# rfid_module_v1.net
KiCad netlist of a schematic drawn in EAGLE
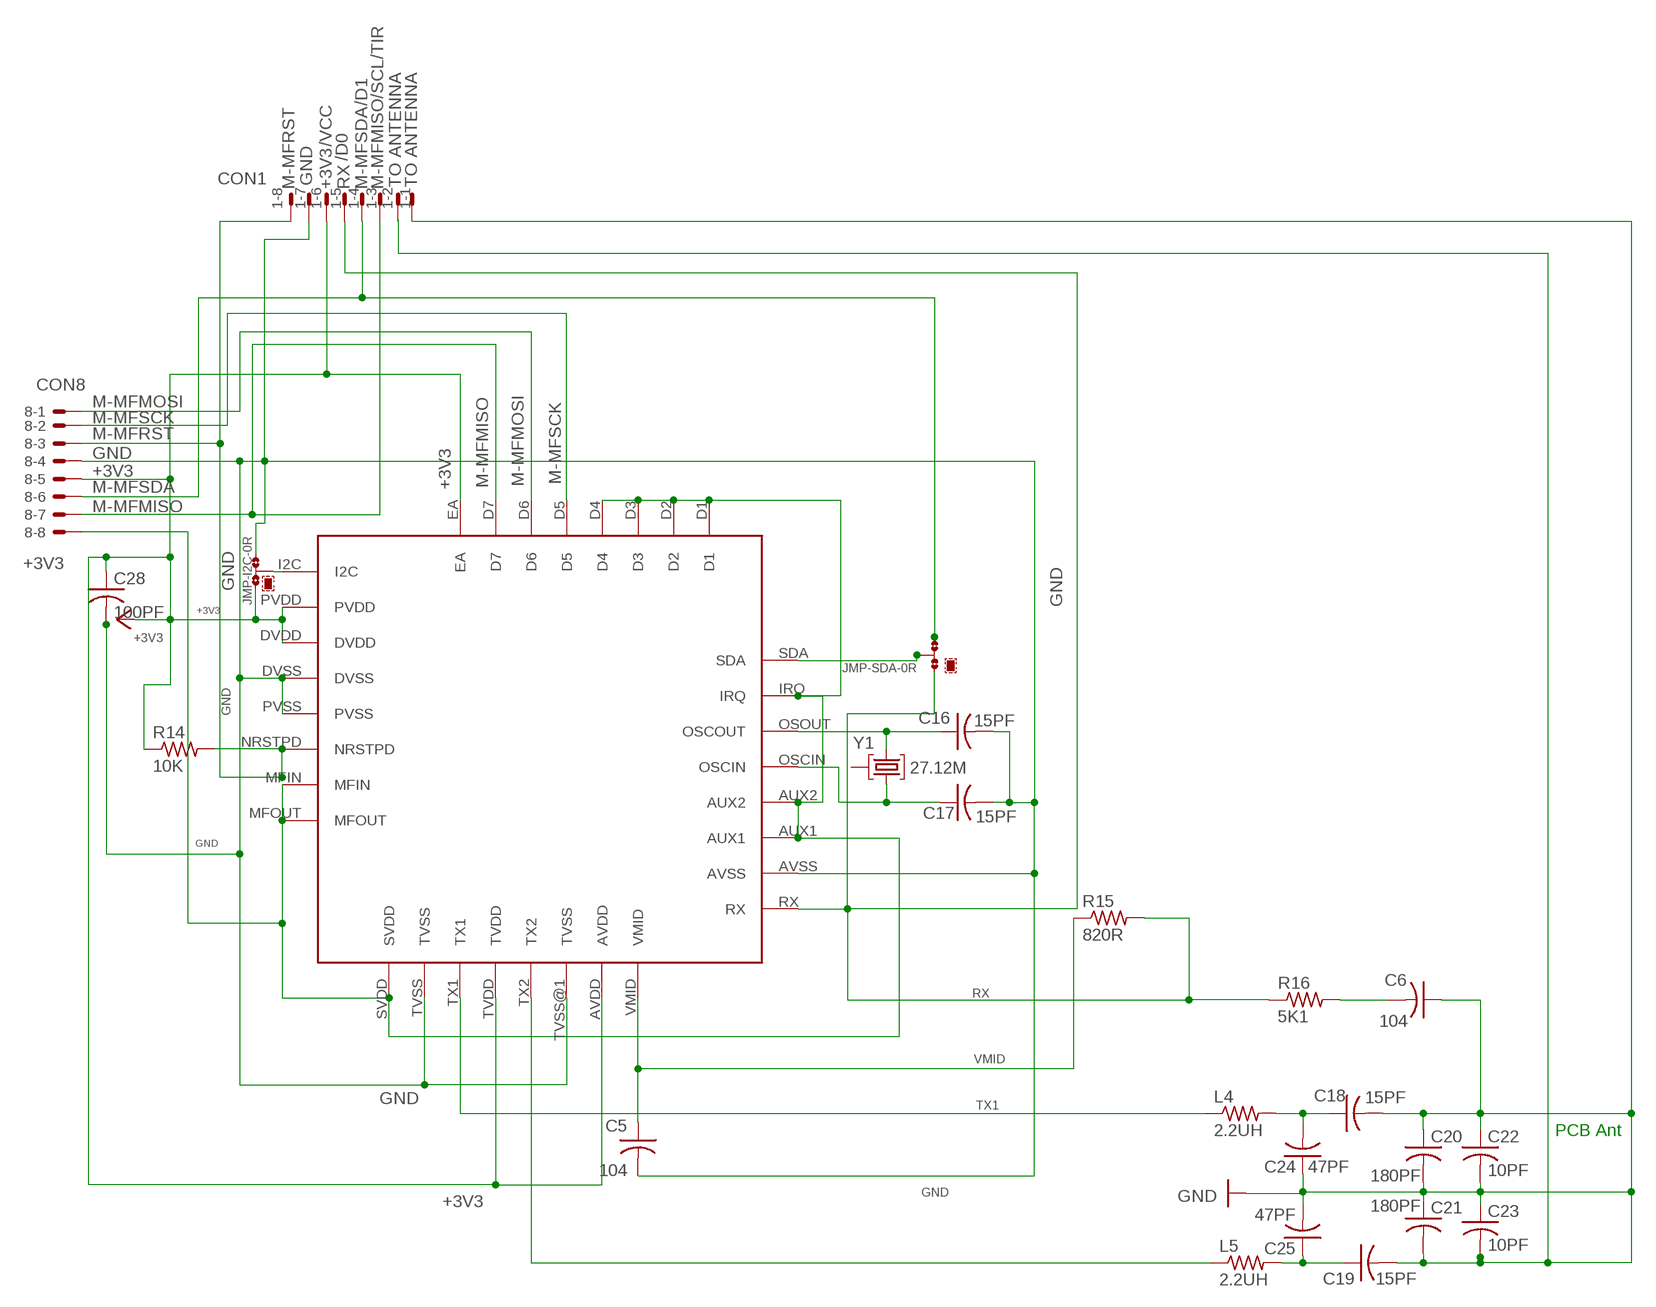
[diagram p0: schematic, sheet 1]

(export (version "E")
  (design (tool "Eeschema 10.0.6"))
  (components
    (comp (ref "1")
      (value "CON1")
      (footprint "eagle-import:22-23-2081")
      (fields (field (name "MF") "MOLEX") (field (name "MPN") "22-23-2081"))
      (libsource (lib "eagle-import") (part "22-23-2081"))
    )
    (comp (ref "8")
      (value "CON8")
      (footprint "eagle-import:22-23-2081")
      (fields (field (name "MF") "MOLEX") (field (name "MPN") "22-23-2081"))
      (libsource (lib "eagle-import") (part "22-23-2081"))
    )
    (comp (ref "C5")
      (value "104")
      (footprint "eagle-import:C0603")
      (libsource (lib "eagle-import") (part "C-USC0603"))
    )
    (comp (ref "C6")
      (value "104")
      (footprint "eagle-import:C0603")
      (libsource (lib "eagle-import") (part "C-USC0603"))
    )
    (comp (ref "C16")
      (value "15PF")
      (footprint "eagle-import:C0603")
      (libsource (lib "eagle-import") (part "C-USC0603"))
    )
    (comp (ref "C17")
      (value "15PF")
      (footprint "eagle-import:C0603")
      (libsource (lib "eagle-import") (part "C-USC0603"))
    )
    (comp (ref "C18")
      (value "15PF")
      (footprint "eagle-import:C0603")
      (libsource (lib "eagle-import") (part "C-USC0603"))
    )
    (comp (ref "C19")
      (value "15PF")
      (footprint "eagle-import:C0603")
      (libsource (lib "eagle-import") (part "C-USC0603"))
    )
    (comp (ref "C20")
      (value "180PF")
      (footprint "eagle-import:C0603")
      (libsource (lib "eagle-import") (part "C-USC0603"))
    )
    (comp (ref "C21")
      (value "180PF")
      (footprint "eagle-import:C0603")
      (libsource (lib "eagle-import") (part "C-USC0603"))
    )
    (comp (ref "C22")
      (value "10PF")
      (footprint "eagle-import:C0603")
      (libsource (lib "eagle-import") (part "C-USC0603"))
    )
    (comp (ref "C23")
      (value "10PF")
      (footprint "eagle-import:C0603")
      (libsource (lib "eagle-import") (part "C-USC0603"))
    )
    (comp (ref "C24")
      (value "47PF")
      (footprint "eagle-import:C0603")
      (libsource (lib "eagle-import") (part "C-USC0603"))
    )
    (comp (ref "C25")
      (value "47PF")
      (footprint "eagle-import:C0603")
      (libsource (lib "eagle-import") (part "C-USC0603"))
    )
    (comp (ref "C28")
      (value "100PF")
      (footprint "eagle-import:C0603")
      (libsource (lib "eagle-import") (part "C-USC0603"))
    )
    (comp (ref "JMP-I2C")
      (value "0R-JUMPA")
      (footprint "eagle-import:A0R-JMP")
      (libsource (lib "eagle-import") (part "0R-JUMPA"))
    )
    (comp (ref "JMP-SDA")
      (value "0R-JUMPA")
      (footprint "eagle-import:A0R-JMP")
      (libsource (lib "eagle-import") (part "0R-JUMPA"))
    )
    (comp (ref "L4")
      (value "2.2UH")
      (footprint "eagle-import:R0603")
      (libsource (lib "eagle-import") (part "R-US_R0603"))
    )
    (comp (ref "L5")
      (value "2.2UH")
      (footprint "eagle-import:R0603")
      (libsource (lib "eagle-import") (part "R-US_R0603"))
    )
    (comp (ref "R14")
      (value "10K")
      (footprint "eagle-import:R0603")
      (libsource (lib "eagle-import") (part "R-US_R0603"))
    )
    (comp (ref "R15")
      (value "820R")
      (footprint "eagle-import:R0603")
      (libsource (lib "eagle-import") (part "R-US_R0603"))
    )
    (comp (ref "R16")
      (value "5K1")
      (footprint "eagle-import:R0603")
      (libsource (lib "eagle-import") (part "R-US_R0603"))
    )
    (comp (ref "U$1")
      (value "MFRC522")
      (footprint "eagle-import:MFRC522")
      (libsource (lib "eagle-import") (part "MFRC522"))
    )
    (comp (ref "Y1")
      (value "27.12M")
      (footprint "eagle-import:RAD3LEAD")
      (libsource (lib "eagle-import") (part "CRYSTAL"))
    )
  )
  (nets
    (net (code "1") (name "+3.3V") (class "Default")
      (node (ref "1") (pin "6") (pinfunction "S_6") (pintype "passive"))
      (node (ref "8") (pin "5") (pinfunction "S_5") (pintype "passive"))
      (node (ref "C28") (pin "1") (pinfunction "1_1") (pintype "passive"))
      (node (ref "JMP-I2C") (pin "3") (pinfunction "3_3") (pintype "passive"))
      (node (ref "R14") (pin "1") (pinfunction "1_1") (pintype "passive"))
      (node (ref "U$1") (pin "AVDD") (pinfunction "AVDD_AVDD") (pintype "bidirectional"))
      (node (ref "U$1") (pin "DVDD") (pinfunction "DVDD_DVDD") (pintype "bidirectional"))
      (node (ref "U$1") (pin "EA") (pinfunction "EA_EA") (pintype "bidirectional"))
      (node (ref "U$1") (pin "PVDD") (pinfunction "PVDD_PVDD") (pintype "bidirectional"))
      (node (ref "U$1") (pin "TVDD") (pinfunction "TVDD_TVDD") (pintype "bidirectional"))
    )
    (net (code "2") (name "/M-MFMISO") (class "Default")
      (node (ref "1") (pin "3") (pinfunction "S_3") (pintype "passive"))
      (node (ref "8") (pin "7") (pinfunction "S_7") (pintype "passive"))
      (node (ref "U$1") (pin "D7") (pinfunction "D7_D7") (pintype "bidirectional"))
    )
    (net (code "3") (name "/M-MFMOSI") (class "Default")
      (node (ref "8") (pin "1") (pinfunction "S_1") (pintype "passive"))
      (node (ref "U$1") (pin "D6") (pinfunction "D6_D6") (pintype "bidirectional"))
    )
    (net (code "4") (name "/M-MFRST") (class "Default")
      (node (ref "1") (pin "8") (pinfunction "S_8") (pintype "passive"))
      (node (ref "8") (pin "3") (pinfunction "S_3") (pintype "passive"))
      (node (ref "R14") (pin "2") (pinfunction "2_2") (pintype "passive"))
      (node (ref "U$1") (pin "NRSTPD") (pinfunction "NRSTPD_NRSTPD") (pintype "bidirectional"))
    )
    (net (code "5") (name "/M-MFSCK") (class "Default")
      (node (ref "8") (pin "2") (pinfunction "S_2") (pintype "passive"))
      (node (ref "U$1") (pin "D5") (pinfunction "D5_D5") (pintype "bidirectional"))
    )
    (net (code "6") (name "/M-MFSDA") (class "Default")
      (node (ref "1") (pin "4") (pinfunction "S_4") (pintype "passive"))
      (node (ref "8") (pin "6") (pinfunction "S_6") (pintype "passive"))
      (node (ref "JMP-SDA") (pin "3") (pinfunction "3_3") (pintype "passive"))
    )
    (net (code "7") (name "/RX") (class "Default")
      (node (ref "1") (pin "5") (pinfunction "S_5") (pintype "passive"))
      (node (ref "JMP-SDA") (pin "1") (pinfunction "1_1") (pintype "passive"))
      (node (ref "R15") (pin "2") (pinfunction "2_2") (pintype "passive"))
      (node (ref "R16") (pin "1") (pinfunction "1_1") (pintype "passive"))
      (node (ref "U$1") (pin "RX") (pinfunction "RX_RX") (pintype "bidirectional"))
    )
    (net (code "8") (name "/TX1") (class "Default")
      (node (ref "L4") (pin "1") (pinfunction "1_1") (pintype "passive"))
      (node (ref "U$1") (pin "TX1") (pinfunction "TX1_TX1") (pintype "bidirectional"))
    )
    (net (code "9") (name "/VMID") (class "Default")
      (node (ref "C5") (pin "1") (pinfunction "1_1") (pintype "passive"))
      (node (ref "R15") (pin "1") (pinfunction "1_1") (pintype "passive"))
      (node (ref "U$1") (pin "VMID") (pinfunction "VMID_VMID") (pintype "bidirectional"))
    )
    (net (code "10") (name "GND") (class "Default")
      (node (ref "1") (pin "1") (pinfunction "S_1") (pintype "passive"))
      (node (ref "1") (pin "7") (pinfunction "S_7") (pintype "passive"))
      (node (ref "8") (pin "4") (pinfunction "S_4") (pintype "passive"))
      (node (ref "C16") (pin "2") (pinfunction "2_2") (pintype "passive"))
      (node (ref "C17") (pin "2") (pinfunction "2_2") (pintype "passive"))
      (node (ref "C18") (pin "2") (pinfunction "2_2") (pintype "passive"))
      (node (ref "C19") (pin "2") (pinfunction "2_2") (pintype "passive"))
      (node (ref "C20") (pin "1") (pinfunction "1_1") (pintype "passive"))
      (node (ref "C20") (pin "2") (pinfunction "2_2") (pintype "passive"))
      (node (ref "C21") (pin "1") (pinfunction "1_1") (pintype "passive"))
      (node (ref "C21") (pin "2") (pinfunction "2_2") (pintype "passive"))
      (node (ref "C22") (pin "1") (pinfunction "1_1") (pintype "passive"))
      (node (ref "C22") (pin "2") (pinfunction "2_2") (pintype "passive"))
      (node (ref "C23") (pin "1") (pinfunction "1_1") (pintype "passive"))
      (node (ref "C23") (pin "2") (pinfunction "2_2") (pintype "passive"))
      (node (ref "C24") (pin "1") (pinfunction "1_1") (pintype "passive"))
      (node (ref "C25") (pin "2") (pinfunction "2_2") (pintype "passive"))
      (node (ref "C28") (pin "2") (pinfunction "2_2") (pintype "passive"))
      (node (ref "C5") (pin "2") (pinfunction "2_2") (pintype "passive"))
      (node (ref "C6") (pin "1") (pinfunction "1_1") (pintype "passive"))
      (node (ref "JMP-I2C") (pin "1") (pinfunction "1_1") (pintype "passive"))
      (node (ref "U$1") (pin "AVSS") (pinfunction "AVSS_AVSS") (pintype "bidirectional"))
      (node (ref "U$1") (pin "DVSS") (pinfunction "DVSS_DVSS") (pintype "bidirectional"))
      (node (ref "U$1") (pin "PVSS") (pinfunction "PVSS_PVSS") (pintype "bidirectional"))
      (node (ref "U$1") (pin "TVSS") (pinfunction "TVSS_TVSS") (pintype "bidirectional"))
      (node (ref "U$1") (pin "TVSS@1") (pinfunction "TVSS_TVSS@1") (pintype "bidirectional"))
    )
    (net (code "11") (name "Net-(8H-S)") (class "Default")
      (node (ref "8") (pin "8") (pinfunction "S_8") (pintype "passive"))
      (node (ref "U$1") (pin "AUX1") (pinfunction "AUX1_AUX1") (pintype "bidirectional"))
      (node (ref "U$1") (pin "AUX2") (pinfunction "AUX2_AUX2") (pintype "bidirectional"))
      (node (ref "U$1") (pin "D1") (pinfunction "D1_D1") (pintype "bidirectional"))
      (node (ref "U$1") (pin "D2") (pinfunction "D2_D2") (pintype "bidirectional"))
      (node (ref "U$1") (pin "D3") (pinfunction "D3_D3") (pintype "bidirectional"))
      (node (ref "U$1") (pin "D4") (pinfunction "D4_D4") (pintype "bidirectional"))
      (node (ref "U$1") (pin "IRQ") (pinfunction "IRQ_IRQ") (pintype "bidirectional"))
      (node (ref "U$1") (pin "MFIN") (pinfunction "MFIN_MFIN") (pintype "bidirectional"))
      (node (ref "U$1") (pin "MFOUT") (pinfunction "MFOUT_MFOUT") (pintype "bidirectional"))
      (node (ref "U$1") (pin "SVDD") (pinfunction "SVDD_SVDD") (pintype "bidirectional"))
    )
    (net (code "12") (name "Net-(C6-Pad2)") (class "Default")
      (node (ref "C6") (pin "2") (pinfunction "2_2") (pintype "passive"))
      (node (ref "R16") (pin "2") (pinfunction "2_2") (pintype "passive"))
    )
    (net (code "13") (name "Net-(C17-Pad1)") (class "Default")
      (node (ref "C17") (pin "1") (pinfunction "1_1") (pintype "passive"))
      (node (ref "U$1") (pin "OSCIN") (pinfunction "OSCIN_OSCIN") (pintype "bidirectional"))
      (node (ref "Y1") (pin "1") (pinfunction "1_1") (pintype "passive"))
    )
    (net (code "14") (name "Net-(C18-Pad1)") (class "Default")
      (node (ref "C18") (pin "1") (pinfunction "1_1") (pintype "passive"))
      (node (ref "C24") (pin "2") (pinfunction "2_2") (pintype "passive"))
      (node (ref "L4") (pin "2") (pinfunction "2_2") (pintype "passive"))
    )
    (net (code "15") (name "Net-(C19-Pad1)") (class "Default")
      (node (ref "C19") (pin "1") (pinfunction "1_1") (pintype "passive"))
      (node (ref "C25") (pin "1") (pinfunction "1_1") (pintype "passive"))
      (node (ref "L5") (pin "2") (pinfunction "2_2") (pintype "passive"))
    )
    (net (code "16") (name "Net-(JMP-I2C-Pad2)") (class "Default")
      (node (ref "JMP-I2C") (pin "2") (pinfunction "2_2") (pintype "passive"))
      (node (ref "U$1") (pin "I2C") (pinfunction "I2C_I2C") (pintype "bidirectional"))
    )
    (net (code "17") (name "Net-(JMP-SDA-Pad2)") (class "Default")
      (node (ref "JMP-SDA") (pin "2") (pinfunction "2_2") (pintype "passive"))
      (node (ref "U$1") (pin "SDA") (pinfunction "SDA_SDA") (pintype "bidirectional"))
    )
    (net (code "18") (name "Net-(L5-Pad1)") (class "Default")
      (node (ref "L5") (pin "1") (pinfunction "1_1") (pintype "passive"))
      (node (ref "U$1") (pin "TX2") (pinfunction "TX2_TX2") (pintype "bidirectional"))
    )
    (net (code "19") (name "Net-(U$1-OSCOUT)") (class "Default")
      (node (ref "C16") (pin "1") (pinfunction "1_1") (pintype "passive"))
      (node (ref "U$1") (pin "OSOUT") (pinfunction "OSCOUT_OSOUT") (pintype "bidirectional"))
      (node (ref "Y1") (pin "3") (pinfunction "3_3") (pintype "passive"))
    )
    (net (code "20") (name "unconnected-(1B-S-Pad2)") (class "Default")
      (node (ref "1") (pin "2") (pinfunction "S_2") (pintype "passive"))
    )
    (net (code "21") (name "unconnected-(Y1-Pad2)") (class "Default")
      (node (ref "Y1") (pin "2") (pinfunction "2_2") (pintype "passive"))
    )
  )
)
